# charivari.net
KiCad netlist of a schematic drawn in EAGLE
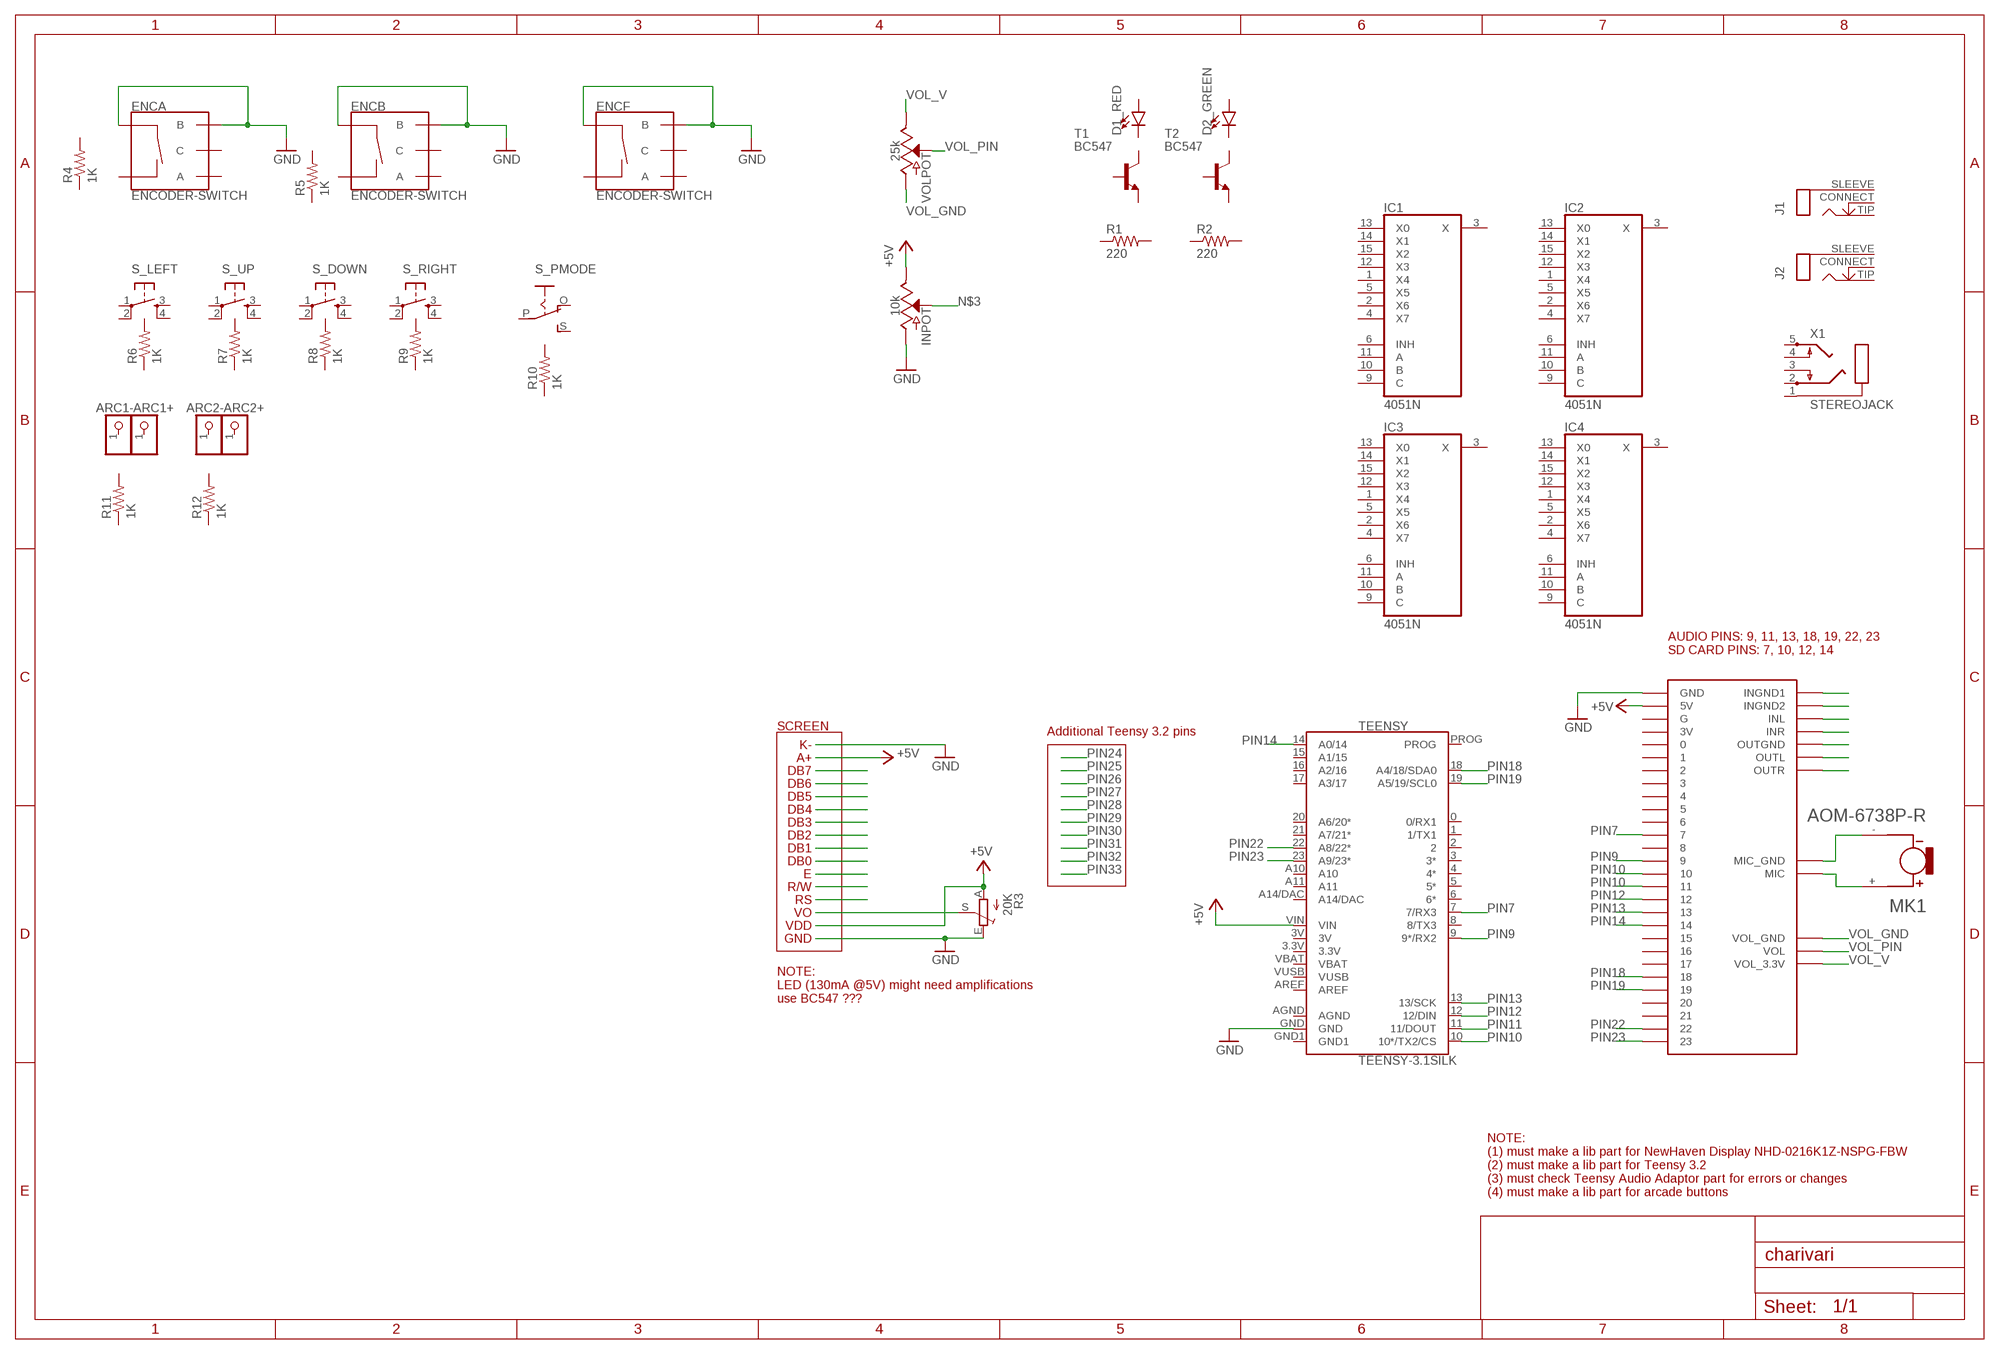
[diagram p0: schematic, sheet 1]

(export (version "E")
  (design (tool "Eeschema 10.0.6"))
  (components
    (comp (ref "ARC1+")
      (value "PINHD-1X1")
      (footprint "eagle-import:1X01")
      (libsource (lib "eagle-import") (part "PINHD-1X1"))
    )
    (comp (ref "ARC1-")
      (value "PINHD-1X1")
      (footprint "eagle-import:1X01")
      (libsource (lib "eagle-import") (part "PINHD-1X1"))
    )
    (comp (ref "ARC2+")
      (value "PINHD-1X1")
      (footprint "eagle-import:1X01")
      (libsource (lib "eagle-import") (part "PINHD-1X1"))
    )
    (comp (ref "ARC2-")
      (value "PINHD-1X1")
      (footprint "eagle-import:1X01")
      (libsource (lib "eagle-import") (part "PINHD-1X1"))
    )
    (comp (ref "AUDIO_ADAPTOR")
      (value "AUDIOSHIELD")
      (footprint "eagle-import:AUDIOSHIELD")
      (libsource (lib "eagle-import") (part "AUDIOSHIELD"))
    )
    (comp (ref "D1_RED")
      (value "LED5MM")
      (footprint "eagle-import:LED_5MM")
      (libsource (lib "eagle-import") (part "LED5MM"))
    )
    (comp (ref "D2_GREEN")
      (value "LED5MM")
      (footprint "eagle-import:LED_5MM")
      (libsource (lib "eagle-import") (part "LED5MM"))
    )
    (comp (ref "ENCA")
      (value "ENCODER-SWITCH")
      (footprint "eagle-import:ROTARY_ENC_PLAIN")
      (libsource (lib "eagle-import") (part "ENCODER-SWITCH"))
    )
    (comp (ref "ENCB")
      (value "ENCODER-SWITCH")
      (footprint "eagle-import:ROTARY_ENC_PLAIN")
      (libsource (lib "eagle-import") (part "ENCODER-SWITCH"))
    )
    (comp (ref "ENCF")
      (value "ENCODER-SWITCH")
      (footprint "eagle-import:ROTARY_ENC_PLAIN")
      (libsource (lib "eagle-import") (part "ENCODER-SWITCH"))
    )
    (comp (ref "IC1")
      (value "4051N")
      (footprint "eagle-import:DIL16")
      (libsource (lib "eagle-import") (part "4051N"))
    )
    (comp (ref "IC2")
      (value "4051N")
      (footprint "eagle-import:DIL16")
      (libsource (lib "eagle-import") (part "4051N"))
    )
    (comp (ref "IC3")
      (value "4051N")
      (footprint "eagle-import:DIL16")
      (libsource (lib "eagle-import") (part "4051N"))
    )
    (comp (ref "IC4")
      (value "4051N")
      (footprint "eagle-import:DIL16")
      (libsource (lib "eagle-import") (part "4051N"))
    )
    (comp (ref "INPOT")
      (value "10k")
      (footprint "eagle-import:POT-PTH-ALPS-KIT")
      (libsource (lib "eagle-import") (part "POTENTIOMETER-PTH-9MM-1/20W-20%-KIT"))
    )
    (comp (ref "J1")
      (value "CLOSEDMONO")
      (footprint "eagle-import:CLOSED_MONO_JACK")
      (libsource (lib "eagle-import") (part "CLOSEDMONO"))
    )
    (comp (ref "J2")
      (value "CLOSEDMONO")
      (footprint "eagle-import:CLOSED_MONO_JACK")
      (libsource (lib "eagle-import") (part "CLOSEDMONO"))
    )
    (comp (ref "MK1")
      (value "AOM-6738P-R")
      (footprint "eagle-import:MIC_AOM-6738P-R")
      (fields (field (name "MF") "PUI"))
      (libsource (lib "eagle-import") (part "AOM-6738P-R"))
    )
    (comp (ref "R1")
      (value "220")
      (footprint "eagle-import:0204_7")
      (libsource (lib "eagle-import") (part "R-US_0204/7"))
    )
    (comp (ref "R2")
      (value "220")
      (footprint "eagle-import:0204_7")
      (libsource (lib "eagle-import") (part "R-US_0204/7"))
    )
    (comp (ref "R3")
      (value "20K")
      (footprint "eagle-import:B25P")
      (libsource (lib "eagle-import") (part "TRIM_EU-B25P"))
    )
    (comp (ref "R4")
      (value "1K")
      (footprint "eagle-import:0204_7")
      (libsource (lib "eagle-import") (part "R-US_0204/7"))
    )
    (comp (ref "R5")
      (value "1K")
      (footprint "eagle-import:0204_7")
      (libsource (lib "eagle-import") (part "R-US_0204/7"))
    )
    (comp (ref "R6")
      (value "1K")
      (footprint "eagle-import:0204_7")
      (libsource (lib "eagle-import") (part "R-US_0204/7"))
    )
    (comp (ref "R7")
      (value "1K")
      (footprint "eagle-import:0204_7")
      (libsource (lib "eagle-import") (part "R-US_0204/7"))
    )
    (comp (ref "R8")
      (value "1K")
      (footprint "eagle-import:0204_7")
      (libsource (lib "eagle-import") (part "R-US_0204/7"))
    )
    (comp (ref "R9")
      (value "1K")
      (footprint "eagle-import:0204_7")
      (libsource (lib "eagle-import") (part "R-US_0204/7"))
    )
    (comp (ref "R10")
      (value "1K")
      (footprint "eagle-import:0204_7")
      (libsource (lib "eagle-import") (part "R-US_0204/7"))
    )
    (comp (ref "R11")
      (value "1K")
      (footprint "eagle-import:0204_7")
      (libsource (lib "eagle-import") (part "R-US_0204/7"))
    )
    (comp (ref "R12")
      (value "1K")
      (footprint "eagle-import:0204_7")
      (libsource (lib "eagle-import") (part "R-US_0204/7"))
    )
    (comp (ref "S_DOWN")
      (value "TAC_SWITCHPTH")
      (footprint "eagle-import:TACTILE-PTH")
      (libsource (lib "eagle-import") (part "TAC_SWITCHPTH"))
    )
    (comp (ref "S_LEFT")
      (value "TAC_SWITCHPTH")
      (footprint "eagle-import:TACTILE-PTH")
      (libsource (lib "eagle-import") (part "TAC_SWITCHPTH"))
    )
    (comp (ref "S_PMODE")
      (value "EG1218S")
      (footprint "eagle-import:EG1218")
      (libsource (lib "eagle-import") (part "EG1218S"))
    )
    (comp (ref "S_RIGHT")
      (value "TAC_SWITCHPTH")
      (footprint "eagle-import:TACTILE-PTH")
      (libsource (lib "eagle-import") (part "TAC_SWITCHPTH"))
    )
    (comp (ref "S_UP")
      (value "TAC_SWITCHPTH")
      (footprint "eagle-import:TACTILE-PTH")
      (libsource (lib "eagle-import") (part "TAC_SWITCHPTH"))
    )
    (comp (ref "T1")
      (value "BC547")
      (footprint "eagle-import:TO92")
      (libsource (lib "eagle-import") (part "BC547"))
    )
    (comp (ref "T2")
      (value "BC547")
      (footprint "eagle-import:TO92")
      (libsource (lib "eagle-import") (part "BC547"))
    )
    (comp (ref "TEENSY")
      (value "TEENSY-3.1SILK")
      (footprint "eagle-import:TEENSY-3.1")
      (libsource (lib "eagle-import") (part "TEENSY-3.1SILK"))
    )
    (comp (ref "VOLPOT")
      (value "25k")
      (footprint "eagle-import:POT-PTH-ALPS-KIT")
      (libsource (lib "eagle-import") (part "POTENTIOMETER-PTH-9MM-1/20W-20%-KIT"))
    )
    (comp (ref "X1")
      (value "STEREOJACK")
      (footprint "eagle-import:STX3100")
      (libsource (lib "eagle-import") (part "STEREOJACK"))
    )
  )
  (nets
    (net (code "1") (name "+5V") (class "Default")
      (node (ref "AUDIO_ADAPTOR") (pin "5V") (pinfunction "5V_5V") (pintype "bidirectional"))
      (node (ref "INPOT") (pin "P$1") (pinfunction "E_P$1") (pintype "passive"))
      (node (ref "R3") (pin "A") (pinfunction "A_A") (pintype "passive"))
      (node (ref "TEENSY") (pin "VIN") (pinfunction "VIN_VIN") (pintype "power_in"))
    )
    (net (code "2") (name "/3.3V") (class "Default")
      (node (ref "TEENSY") (pin "3.3V") (pinfunction "3.3V_3.3V") (pintype "power_in"))
    )
    (net (code "3") (name "/3V") (class "Default")
      (node (ref "TEENSY") (pin "3V") (pinfunction "3V_3V") (pintype "power_in"))
    )
    (net (code "4") (name "/AGND") (class "Default")
      (node (ref "TEENSY") (pin "AGND") (pinfunction "AGND_AGND") (pintype "power_in"))
    )
    (net (code "5") (name "/GND1") (class "Default")
      (node (ref "TEENSY") (pin "GND1") (pinfunction "GND1_GND1") (pintype "power_in"))
    )
    (net (code "6") (name "/N$3") (class "Default")
      (node (ref "INPOT") (pin "P$2") (pinfunction "S_P$2") (pintype "passive"))
    )
    (net (code "7") (name "/PIN7") (class "Default")
      (node (ref "AUDIO_ADAPTOR") (pin "7") (pinfunction "7_7") (pintype "bidirectional"))
      (node (ref "TEENSY") (pin "7") (pinfunction "7/RX3_7") (pintype "bidirectional"))
    )
    (net (code "8") (name "/PIN9") (class "Default")
      (node (ref "AUDIO_ADAPTOR") (pin "9") (pinfunction "9_9") (pintype "bidirectional"))
      (node (ref "TEENSY") (pin "9") (pinfunction "9*/RX2_9") (pintype "bidirectional"))
    )
    (net (code "9") (name "/PIN10") (class "Default")
      (node (ref "AUDIO_ADAPTOR") (pin "10") (pinfunction "10_10") (pintype "bidirectional"))
      (node (ref "AUDIO_ADAPTOR") (pin "11") (pinfunction "11_11") (pintype "bidirectional"))
      (node (ref "TEENSY") (pin "10") (pinfunction "10*/TX2/CS_10") (pintype "bidirectional"))
    )
    (net (code "10") (name "/PIN11") (class "Default")
      (node (ref "TEENSY") (pin "11") (pinfunction "11/DOUT_11") (pintype "bidirectional"))
    )
    (net (code "11") (name "/PIN12") (class "Default")
      (node (ref "AUDIO_ADAPTOR") (pin "12") (pinfunction "12_12") (pintype "bidirectional"))
      (node (ref "TEENSY") (pin "12") (pinfunction "12/DIN_12") (pintype "bidirectional"))
    )
    (net (code "12") (name "/PIN13") (class "Default")
      (node (ref "AUDIO_ADAPTOR") (pin "13") (pinfunction "13_13") (pintype "bidirectional"))
      (node (ref "TEENSY") (pin "13") (pinfunction "13/SCK_13") (pintype "bidirectional"))
    )
    (net (code "13") (name "/PIN14") (class "Default")
      (node (ref "AUDIO_ADAPTOR") (pin "14") (pinfunction "14_14") (pintype "bidirectional"))
      (node (ref "TEENSY") (pin "14") (pinfunction "A0/14_14") (pintype "bidirectional"))
    )
    (net (code "14") (name "/PIN18") (class "Default")
      (node (ref "AUDIO_ADAPTOR") (pin "18") (pinfunction "18_18") (pintype "bidirectional"))
      (node (ref "TEENSY") (pin "18") (pinfunction "A4/18/SDA0_18") (pintype "bidirectional"))
    )
    (net (code "15") (name "/PIN19") (class "Default")
      (node (ref "AUDIO_ADAPTOR") (pin "19") (pinfunction "19_19") (pintype "bidirectional"))
      (node (ref "TEENSY") (pin "19") (pinfunction "A5/19/SCL0_19") (pintype "bidirectional"))
    )
    (net (code "16") (name "/PIN22") (class "Default")
      (node (ref "AUDIO_ADAPTOR") (pin "22") (pinfunction "22_22") (pintype "bidirectional"))
      (node (ref "TEENSY") (pin "22") (pinfunction "A8/22*_22") (pintype "bidirectional"))
    )
    (net (code "17") (name "/PIN23") (class "Default")
      (node (ref "AUDIO_ADAPTOR") (pin "23") (pinfunction "23_23") (pintype "bidirectional"))
      (node (ref "TEENSY") (pin "23") (pinfunction "A9/23*_23") (pintype "bidirectional"))
    )
    (net (code "28") (name "/VBAT") (class "Default")
      (node (ref "TEENSY") (pin "VBAT") (pinfunction "VBAT_VBAT") (pintype "power_in"))
    )
    (net (code "29") (name "/VOL_GND") (class "Default")
      (node (ref "AUDIO_ADAPTOR") (pin "VOL_GND") (pinfunction "VOL_GND_VOL_GND") (pintype "bidirectional"))
      (node (ref "VOLPOT") (pin "P$3") (pinfunction "A_P$3") (pintype "passive"))
    )
    (net (code "30") (name "/VOL_PIN") (class "Default")
      (node (ref "AUDIO_ADAPTOR") (pin "VOL") (pinfunction "VOL_VOL") (pintype "input"))
      (node (ref "VOLPOT") (pin "P$2") (pinfunction "S_P$2") (pintype "passive"))
    )
    (net (code "31") (name "/VOL_V") (class "Default")
      (node (ref "AUDIO_ADAPTOR") (pin "VOL_3.3V") (pinfunction "VOL_3.3V_VOL_3.3V") (pintype "bidirectional"))
      (node (ref "VOLPOT") (pin "P$1") (pinfunction "E_P$1") (pintype "passive"))
    )
    (net (code "32") (name "/VUSB") (class "Default")
      (node (ref "TEENSY") (pin "VUSB") (pinfunction "VUSB_VUSB") (pintype "power_in"))
    )
    (net (code "33") (name "GND") (class "Default")
      (node (ref "AUDIO_ADAPTOR") (pin "GND") (pinfunction "GND_GND") (pintype "bidirectional"))
      (node (ref "ENCA") (pin "B") (pinfunction "B_B") (pintype "bidirectional"))
      (node (ref "ENCA") (pin "SW+") (pinfunction "SW+_SW+") (pintype "bidirectional"))
      (node (ref "ENCB") (pin "B") (pinfunction "B_B") (pintype "bidirectional"))
      (node (ref "ENCB") (pin "SW+") (pinfunction "SW+_SW+") (pintype "bidirectional"))
      (node (ref "ENCF") (pin "B") (pinfunction "B_B") (pintype "bidirectional"))
      (node (ref "ENCF") (pin "SW+") (pinfunction "SW+_SW+") (pintype "bidirectional"))
      (node (ref "INPOT") (pin "P$3") (pinfunction "A_P$3") (pintype "passive"))
      (node (ref "R3") (pin "E") (pinfunction "E_E") (pintype "passive"))
      (node (ref "TEENSY") (pin "GND") (pinfunction "GND_GND") (pintype "power_in"))
    )
    (net (code "34") (name "Net-(AUDIO_ADAPTOR-MIC_GND)") (class "Default")
      (node (ref "AUDIO_ADAPTOR") (pin "GND_MIC") (pinfunction "MIC_GND_GND_MIC") (pintype "bidirectional"))
      (node (ref "MK1") (pin "-") (pinfunction "-_-") (pintype "passive"))
    )
    (net (code "35") (name "Net-(AUDIO_ADAPTOR-PadMIC)") (class "Default")
      (node (ref "AUDIO_ADAPTOR") (pin "MIC") (pinfunction "MIC_MIC") (pintype "input"))
      (node (ref "MK1") (pin "+") (pinfunction "+_+") (pintype "passive"))
    )
    (net (code "36") (name "unconnected-(ARC1+-Pad1)") (class "Default")
      (node (ref "ARC1+") (pin "1") (pinfunction "1_1") (pintype "passive"))
    )
    (net (code "37") (name "unconnected-(ARC1--Pad1)") (class "Default")
      (node (ref "ARC1-") (pin "1") (pinfunction "1_1") (pintype "passive"))
    )
    (net (code "38") (name "unconnected-(ARC2+-Pad1)") (class "Default")
      (node (ref "ARC2+") (pin "1") (pinfunction "1_1") (pintype "passive"))
    )
    (net (code "39") (name "unconnected-(ARC2--Pad1)") (class "Default")
      (node (ref "ARC2-") (pin "1") (pinfunction "1_1") (pintype "passive"))
    )
    (net (code "40") (name "unconnected-(AUDIO_ADAPTOR-Pad0)") (class "Default")
      (node (ref "AUDIO_ADAPTOR") (pin "0") (pinfunction "0_0") (pintype "bidirectional"))
    )
    (net (code "41") (name "unconnected-(AUDIO_ADAPTOR-Pad1)") (class "Default")
      (node (ref "AUDIO_ADAPTOR") (pin "1") (pinfunction "1_1") (pintype "bidirectional"))
    )
    (net (code "42") (name "unconnected-(AUDIO_ADAPTOR-Pad2)") (class "Default")
      (node (ref "AUDIO_ADAPTOR") (pin "2") (pinfunction "2_2") (pintype "bidirectional"))
    )
    (net (code "43") (name "unconnected-(AUDIO_ADAPTOR-Pad3)") (class "Default")
      (node (ref "AUDIO_ADAPTOR") (pin "3") (pinfunction "3_3") (pintype "bidirectional"))
    )
    (net (code "44") (name "unconnected-(AUDIO_ADAPTOR-Pad3V)") (class "Default")
      (node (ref "AUDIO_ADAPTOR") (pin "3V") (pinfunction "3V_3V") (pintype "bidirectional"))
    )
    (net (code "45") (name "unconnected-(AUDIO_ADAPTOR-Pad4)") (class "Default")
      (node (ref "AUDIO_ADAPTOR") (pin "4") (pinfunction "4_4") (pintype "bidirectional"))
    )
    (net (code "46") (name "unconnected-(AUDIO_ADAPTOR-Pad5)") (class "Default")
      (node (ref "AUDIO_ADAPTOR") (pin "5") (pinfunction "5_5") (pintype "bidirectional"))
    )
    (net (code "47") (name "unconnected-(AUDIO_ADAPTOR-Pad6)") (class "Default")
      (node (ref "AUDIO_ADAPTOR") (pin "6") (pinfunction "6_6") (pintype "bidirectional"))
    )
    (net (code "48") (name "unconnected-(AUDIO_ADAPTOR-Pad8)") (class "Default")
      (node (ref "AUDIO_ADAPTOR") (pin "8") (pinfunction "8_8") (pintype "bidirectional"))
    )
    (net (code "49") (name "unconnected-(AUDIO_ADAPTOR-Pad15)") (class "Default")
      (node (ref "AUDIO_ADAPTOR") (pin "15") (pinfunction "15_15") (pintype "bidirectional"))
    )
    (net (code "50") (name "unconnected-(AUDIO_ADAPTOR-Pad16)") (class "Default")
      (node (ref "AUDIO_ADAPTOR") (pin "16") (pinfunction "16_16") (pintype "bidirectional"))
    )
    (net (code "51") (name "unconnected-(AUDIO_ADAPTOR-Pad17)") (class "Default")
      (node (ref "AUDIO_ADAPTOR") (pin "17") (pinfunction "17_17") (pintype "bidirectional"))
    )
    (net (code "52") (name "unconnected-(AUDIO_ADAPTOR-Pad20)") (class "Default")
      (node (ref "AUDIO_ADAPTOR") (pin "20") (pinfunction "20_20") (pintype "bidirectional"))
    )
    (net (code "53") (name "unconnected-(AUDIO_ADAPTOR-Pad21)") (class "Default")
      (node (ref "AUDIO_ADAPTOR") (pin "21") (pinfunction "21_21") (pintype "bidirectional"))
    )
    (net (code "54") (name "unconnected-(AUDIO_ADAPTOR-PadG)") (class "Default")
      (node (ref "AUDIO_ADAPTOR") (pin "G") (pinfunction "G_G") (pintype "bidirectional"))
    )
    (net (code "55") (name "unconnected-(AUDIO_ADAPTOR-PadINGND1)") (class "Default")
      (node (ref "AUDIO_ADAPTOR") (pin "INGND1") (pinfunction "INGND1_INGND1") (pintype "bidirectional"))
    )
    (net (code "56") (name "unconnected-(AUDIO_ADAPTOR-PadINGND2)") (class "Default")
      (node (ref "AUDIO_ADAPTOR") (pin "INGND2") (pinfunction "INGND2_INGND2") (pintype "bidirectional"))
    )
    (net (code "57") (name "unconnected-(AUDIO_ADAPTOR-PadINL)") (class "Default")
      (node (ref "AUDIO_ADAPTOR") (pin "INL") (pinfunction "INL_INL") (pintype "input"))
    )
    (net (code "58") (name "unconnected-(AUDIO_ADAPTOR-PadINR)") (class "Default")
      (node (ref "AUDIO_ADAPTOR") (pin "INR") (pinfunction "INR_INR") (pintype "input"))
    )
    (net (code "59") (name "unconnected-(AUDIO_ADAPTOR-PadOUTGND)") (class "Default")
      (node (ref "AUDIO_ADAPTOR") (pin "OUTGND") (pinfunction "OUTGND_OUTGND") (pintype "bidirectional"))
    )
    (net (code "60") (name "unconnected-(AUDIO_ADAPTOR-PadOUTL)") (class "Default")
      (node (ref "AUDIO_ADAPTOR") (pin "OUTL") (pinfunction "OUTL_OUTL") (pintype "output"))
    )
    (net (code "61") (name "unconnected-(AUDIO_ADAPTOR-PadOUTR)") (class "Default")
      (node (ref "AUDIO_ADAPTOR") (pin "OUTR") (pinfunction "OUTR_OUTR") (pintype "output"))
    )
    (net (code "62") (name "unconnected-(D1_RED-C-PadK)") (class "Default")
      (node (ref "D1_RED") (pin "K") (pinfunction "C_K") (pintype "passive"))
    )
    (net (code "63") (name "unconnected-(D1_RED-PadA)") (class "Default")
      (node (ref "D1_RED") (pin "A") (pinfunction "A_A") (pintype "passive"))
    )
    (net (code "64") (name "unconnected-(D2_GREEN-C-PadK)") (class "Default")
      (node (ref "D2_GREEN") (pin "K") (pinfunction "C_K") (pintype "passive"))
    )
    (net (code "65") (name "unconnected-(D2_GREEN-PadA)") (class "Default")
      (node (ref "D2_GREEN") (pin "A") (pinfunction "A_A") (pintype "passive"))
    )
    (net (code "66") (name "unconnected-(ENCA-PadA)") (class "Default")
      (node (ref "ENCA") (pin "A") (pinfunction "A_A") (pintype "bidirectional"))
    )
    (net (code "67") (name "unconnected-(ENCA-PadC)") (class "Default")
      (node (ref "ENCA") (pin "C") (pinfunction "C_C") (pintype "bidirectional"))
    )
    (net (code "68") (name "unconnected-(ENCA-PadSW-)") (class "Default")
      (node (ref "ENCA") (pin "SW-") (pinfunction "SW-_SW-") (pintype "bidirectional"))
    )
    (net (code "69") (name "unconnected-(ENCB-PadA)") (class "Default")
      (node (ref "ENCB") (pin "A") (pinfunction "A_A") (pintype "bidirectional"))
    )
    (net (code "70") (name "unconnected-(ENCB-PadC)") (class "Default")
      (node (ref "ENCB") (pin "C") (pinfunction "C_C") (pintype "bidirectional"))
    )
    (net (code "71") (name "unconnected-(ENCB-PadSW-)") (class "Default")
      (node (ref "ENCB") (pin "SW-") (pinfunction "SW-_SW-") (pintype "bidirectional"))
    )
    (net (code "72") (name "unconnected-(ENCF-PadA)") (class "Default")
      (node (ref "ENCF") (pin "A") (pinfunction "A_A") (pintype "bidirectional"))
    )
    (net (code "73") (name "unconnected-(ENCF-PadC)") (class "Default")
      (node (ref "ENCF") (pin "C") (pinfunction "C_C") (pintype "bidirectional"))
    )
    (net (code "74") (name "unconnected-(ENCF-PadSW-)") (class "Default")
      (node (ref "ENCF") (pin "SW-") (pinfunction "SW-_SW-") (pintype "bidirectional"))
    )
    (net (code "75") (name "unconnected-(IC1A-A-Pad11)") (class "Default")
      (node (ref "IC1") (pin "11") (pinfunction "A_11") (pintype "input"))
    )
    (net (code "76") (name "unconnected-(IC1A-B-Pad10)") (class "Default")
      (node (ref "IC1") (pin "10") (pinfunction "B_10") (pintype "input"))
    )
    (net (code "77") (name "unconnected-(IC1A-C-Pad9)") (class "Default")
      (node (ref "IC1") (pin "9") (pinfunction "C_9") (pintype "input"))
    )
    (net (code "78") (name "unconnected-(IC1A-INH-Pad6)") (class "Default")
      (node (ref "IC1") (pin "6") (pinfunction "INH_6") (pintype "input"))
    )
    (net (code "79") (name "unconnected-(IC1A-X-Pad3)") (class "Default")
      (node (ref "IC1") (pin "3") (pinfunction "X_3") (pintype "bidirectional"))
    )
    (net (code "80") (name "unconnected-(IC1A-X0-Pad13)") (class "Default")
      (node (ref "IC1") (pin "13") (pinfunction "X0_13") (pintype "bidirectional"))
    )
    (net (code "81") (name "unconnected-(IC1A-X1-Pad14)") (class "Default")
      (node (ref "IC1") (pin "14") (pinfunction "X1_14") (pintype "bidirectional"))
    )
    (net (code "82") (name "unconnected-(IC1A-X2-Pad15)") (class "Default")
      (node (ref "IC1") (pin "15") (pinfunction "X2_15") (pintype "bidirectional"))
    )
    (net (code "83") (name "unconnected-(IC1A-X3-Pad12)") (class "Default")
      (node (ref "IC1") (pin "12") (pinfunction "X3_12") (pintype "bidirectional"))
    )
    (net (code "84") (name "unconnected-(IC1A-X4-Pad1)") (class "Default")
      (node (ref "IC1") (pin "1") (pinfunction "X4_1") (pintype "bidirectional"))
    )
    (net (code "85") (name "unconnected-(IC1A-X5-Pad5)") (class "Default")
      (node (ref "IC1") (pin "5") (pinfunction "X5_5") (pintype "bidirectional"))
    )
    (net (code "86") (name "unconnected-(IC1A-X6-Pad2)") (class "Default")
      (node (ref "IC1") (pin "2") (pinfunction "X6_2") (pintype "bidirectional"))
    )
    (net (code "87") (name "unconnected-(IC1A-X7-Pad4)") (class "Default")
      (node (ref "IC1") (pin "4") (pinfunction "X7_4") (pintype "bidirectional"))
    )
    (net (code "88") (name "unconnected-(IC2A-A-Pad11)") (class "Default")
      (node (ref "IC2") (pin "11") (pinfunction "A_11") (pintype "input"))
    )
    (net (code "89") (name "unconnected-(IC2A-B-Pad10)") (class "Default")
      (node (ref "IC2") (pin "10") (pinfunction "B_10") (pintype "input"))
    )
    (net (code "90") (name "unconnected-(IC2A-C-Pad9)") (class "Default")
      (node (ref "IC2") (pin "9") (pinfunction "C_9") (pintype "input"))
    )
    (net (code "91") (name "unconnected-(IC2A-INH-Pad6)") (class "Default")
      (node (ref "IC2") (pin "6") (pinfunction "INH_6") (pintype "input"))
    )
    (net (code "92") (name "unconnected-(IC2A-X-Pad3)") (class "Default")
      (node (ref "IC2") (pin "3") (pinfunction "X_3") (pintype "bidirectional"))
    )
    (net (code "93") (name "unconnected-(IC2A-X0-Pad13)") (class "Default")
      (node (ref "IC2") (pin "13") (pinfunction "X0_13") (pintype "bidirectional"))
    )
    (net (code "94") (name "unconnected-(IC2A-X1-Pad14)") (class "Default")
      (node (ref "IC2") (pin "14") (pinfunction "X1_14") (pintype "bidirectional"))
    )
    (net (code "95") (name "unconnected-(IC2A-X2-Pad15)") (class "Default")
      (node (ref "IC2") (pin "15") (pinfunction "X2_15") (pintype "bidirectional"))
    )
    (net (code "96") (name "unconnected-(IC2A-X3-Pad12)") (class "Default")
      (node (ref "IC2") (pin "12") (pinfunction "X3_12") (pintype "bidirectional"))
    )
    (net (code "97") (name "unconnected-(IC2A-X4-Pad1)") (class "Default")
      (node (ref "IC2") (pin "1") (pinfunction "X4_1") (pintype "bidirectional"))
    )
    (net (code "98") (name "unconnected-(IC2A-X5-Pad5)") (class "Default")
      (node (ref "IC2") (pin "5") (pinfunction "X5_5") (pintype "bidirectional"))
    )
    (net (code "99") (name "unconnected-(IC2A-X6-Pad2)") (class "Default")
      (node (ref "IC2") (pin "2") (pinfunction "X6_2") (pintype "bidirectional"))
    )
    (net (code "100") (name "unconnected-(IC2A-X7-Pad4)") (class "Default")
      (node (ref "IC2") (pin "4") (pinfunction "X7_4") (pintype "bidirectional"))
    )
    (net (code "101") (name "unconnected-(IC3A-A-Pad11)") (class "Default")
      (node (ref "IC3") (pin "11") (pinfunction "A_11") (pintype "input"))
    )
    (net (code "102") (name "unconnected-(IC3A-B-Pad10)") (class "Default")
      (node (ref "IC3") (pin "10") (pinfunction "B_10") (pintype "input"))
    )
    (net (code "103") (name "unconnected-(IC3A-C-Pad9)") (class "Default")
      (node (ref "IC3") (pin "9") (pinfunction "C_9") (pintype "input"))
    )
    (net (code "104") (name "unconnected-(IC3A-INH-Pad6)") (class "Default")
      (node (ref "IC3") (pin "6") (pinfunction "INH_6") (pintype "input"))
    )
    (net (code "105") (name "unconnected-(IC3A-X-Pad3)") (class "Default")
      (node (ref "IC3") (pin "3") (pinfunction "X_3") (pintype "bidirectional"))
    )
    (net (code "106") (name "unconnected-(IC3A-X0-Pad13)") (class "Default")
      (node (ref "IC3") (pin "13") (pinfunction "X0_13") (pintype "bidirectional"))
    )
    (net (code "107") (name "unconnected-(IC3A-X1-Pad14)") (class "Default")
      (node (ref "IC3") (pin "14") (pinfunction "X1_14") (pintype "bidirectional"))
    )
    (net (code "108") (name "unconnected-(IC3A-X2-Pad15)") (class "Default")
      (node (ref "IC3") (pin "15") (pinfunction "X2_15") (pintype "bidirectional"))
    )
    (net (code "109") (name "unconnected-(IC3A-X3-Pad12)") (class "Default")
      (node (ref "IC3") (pin "12") (pinfunction "X3_12") (pintype "bidirectional"))
    )
    (net (code "110") (name "unconnected-(IC3A-X4-Pad1)") (class "Default")
      (node (ref "IC3") (pin "1") (pinfunction "X4_1") (pintype "bidirectional"))
    )
    (net (code "111") (name "unconnected-(IC3A-X5-Pad5)") (class "Default")
      (node (ref "IC3") (pin "5") (pinfunction "X5_5") (pintype "bidirectional"))
    )
    (net (code "112") (name "unconnected-(IC3A-X6-Pad2)") (class "Default")
      (node (ref "IC3") (pin "2") (pinfunction "X6_2") (pintype "bidirectional"))
    )
    (net (code "113") (name "unconnected-(IC3A-X7-Pad4)") (class "Default")
      (node (ref "IC3") (pin "4") (pinfunction "X7_4") (pintype "bidirectional"))
    )
    (net (code "114") (name "unconnected-(IC4A-A-Pad11)") (class "Default")
      (node (ref "IC4") (pin "11") (pinfunction "A_11") (pintype "input"))
    )
    (net (code "115") (name "unconnected-(IC4A-B-Pad10)") (class "Default")
      (node (ref "IC4") (pin "10") (pinfunction "B_10") (pintype "input"))
    )
    (net (code "116") (name "unconnected-(IC4A-C-Pad9)") (class "Default")
      (node (ref "IC4") (pin "9") (pinfunction "C_9") (pintype "input"))
    )
    (net (code "117") (name "unconnected-(IC4A-INH-Pad6)") (class "Default")
      (node (ref "IC4") (pin "6") (pinfunction "INH_6") (pintype "input"))
    )
    (net (code "118") (name "unconnected-(IC4A-X-Pad3)") (class "Default")
      (node (ref "IC4") (pin "3") (pinfunction "X_3") (pintype "bidirectional"))
    )
    (net (code "119") (name "unconnected-(IC4A-X0-Pad13)") (class "Default")
      (node (ref "IC4") (pin "13") (pinfunction "X0_13") (pintype "bidirectional"))
    )
    (net (code "120") (name "unconnected-(IC4A-X1-Pad14)") (class "Default")
      (node (ref "IC4") (pin "14") (pinfunction "X1_14") (pintype "bidirectional"))
    )
    (net (code "121") (name "unconnected-(IC4A-X2-Pad15)") (class "Default")
      (node (ref "IC4") (pin "15") (pinfunction "X2_15") (pintype "bidirectional"))
    )
    (net (code "122") (name "unconnected-(IC4A-X3-Pad12)") (class "Default")
      (node (ref "IC4") (pin "12") (pinfunction "X3_12") (pintype "bidirectional"))
    )
    (net (code "123") (name "unconnected-(IC4A-X4-Pad1)") (class "Default")
      (node (ref "IC4") (pin "1") (pinfunction "X4_1") (pintype "bidirectional"))
    )
    (net (code "124") (name "unconnected-(IC4A-X5-Pad5)") (class "Default")
      (node (ref "IC4") (pin "5") (pinfunction "X5_5") (pintype "bidirectional"))
    )
    (net (code "125") (name "unconnected-(IC4A-X6-Pad2)") (class "Default")
      (node (ref "IC4") (pin "2") (pinfunction "X6_2") (pintype "bidirectional"))
    )
    (net (code "126") (name "unconnected-(IC4A-X7-Pad4)") (class "Default")
      (node (ref "IC4") (pin "4") (pinfunction "X7_4") (pintype "bidirectional"))
    )
    (net (code "127") (name "unconnected-(J1-PadCONNECT)") (class "Default")
      (node (ref "J1") (pin "CONNECT") (pinfunction "CONNECT_CONNECT") (pintype "passive"))
    )
    (net (code "128") (name "unconnected-(J1-PadTIP)") (class "Default")
      (node (ref "J1") (pin "TIP") (pinfunction "TIP_TIP") (pintype "passive"))
    )
    (net (code "129") (name "unconnected-(J1-RING-PadSLEEVE)") (class "Default")
      (node (ref "J1") (pin "SLEEVE") (pinfunction "RING_SLEEVE") (pintype "passive"))
    )
    (net (code "130") (name "unconnected-(J2-PadCONNECT)") (class "Default")
      (node (ref "J2") (pin "CONNECT") (pinfunction "CONNECT_CONNECT") (pintype "passive"))
    )
    (net (code "131") (name "unconnected-(J2-PadTIP)") (class "Default")
      (node (ref "J2") (pin "TIP") (pinfunction "TIP_TIP") (pintype "passive"))
    )
    (net (code "132") (name "unconnected-(J2-RING-PadSLEEVE)") (class "Default")
      (node (ref "J2") (pin "SLEEVE") (pinfunction "RING_SLEEVE") (pintype "passive"))
    )
    (net (code "133") (name "unconnected-(R1-Pad1)") (class "Default")
      (node (ref "R1") (pin "1") (pinfunction "1_1") (pintype "passive"))
    )
    (net (code "134") (name "unconnected-(R1-Pad2)") (class "Default")
      (node (ref "R1") (pin "2") (pinfunction "2_2") (pintype "passive"))
    )
    (net (code "135") (name "unconnected-(R2-Pad1)") (class "Default")
      (node (ref "R2") (pin "1") (pinfunction "1_1") (pintype "passive"))
    )
    (net (code "136") (name "unconnected-(R2-Pad2)") (class "Default")
      (node (ref "R2") (pin "2") (pinfunction "2_2") (pintype "passive"))
    )
    (net (code "137") (name "unconnected-(R3-PadS)") (class "Default")
      (node (ref "R3") (pin "S") (pinfunction "S_S") (pintype "passive"))
    )
    (net (code "138") (name "unconnected-(R4-Pad1)") (class "Default")
      (node (ref "R4") (pin "1") (pinfunction "1_1") (pintype "passive"))
    )
    (net (code "139") (name "unconnected-(R4-Pad2)") (class "Default")
      (node (ref "R4") (pin "2") (pinfunction "2_2") (pintype "passive"))
    )
    (net (code "140") (name "unconnected-(R5-Pad1)") (class "Default")
      (node (ref "R5") (pin "1") (pinfunction "1_1") (pintype "passive"))
    )
    (net (code "141") (name "unconnected-(R5-Pad2)") (class "Default")
      (node (ref "R5") (pin "2") (pinfunction "2_2") (pintype "passive"))
    )
    (net (code "142") (name "unconnected-(R6-Pad1)") (class "Default")
      (node (ref "R6") (pin "1") (pinfunction "1_1") (pintype "passive"))
    )
    (net (code "143") (name "unconnected-(R6-Pad2)") (class "Default")
      (node (ref "R6") (pin "2") (pinfunction "2_2") (pintype "passive"))
    )
    (net (code "144") (name "unconnected-(R7-Pad1)") (class "Default")
      (node (ref "R7") (pin "1") (pinfunction "1_1") (pintype "passive"))
    )
    (net (code "145") (name "unconnected-(R7-Pad2)") (class "Default")
      (node (ref "R7") (pin "2") (pinfunction "2_2") (pintype "passive"))
    )
    (net (code "146") (name "unconnected-(R8-Pad1)") (class "Default")
      (node (ref "R8") (pin "1") (pinfunction "1_1") (pintype "passive"))
    )
    (net (code "147") (name "unconnected-(R8-Pad2)") (class "Default")
      (node (ref "R8") (pin "2") (pinfunction "2_2") (pintype "passive"))
    )
    (net (code "148") (name "unconnected-(R9-Pad1)") (class "Default")
      (node (ref "R9") (pin "1") (pinfunction "1_1") (pintype "passive"))
    )
    (net (code "149") (name "unconnected-(R9-Pad2)") (class "Default")
      (node (ref "R9") (pin "2") (pinfunction "2_2") (pintype "passive"))
    )
    (net (code "150") (name "unconnected-(R10-Pad1)") (class "Default")
      (node (ref "R10") (pin "1") (pinfunction "1_1") (pintype "passive"))
    )
    (net (code "151") (name "unconnected-(R10-Pad2)") (class "Default")
      (node (ref "R10") (pin "2") (pinfunction "2_2") (pintype "passive"))
    )
    (net (code "152") (name "unconnected-(R11-Pad1)") (class "Default")
      (node (ref "R11") (pin "1") (pinfunction "1_1") (pintype "passive"))
    )
    (net (code "153") (name "unconnected-(R11-Pad2)") (class "Default")
      (node (ref "R11") (pin "2") (pinfunction "2_2") (pintype "passive"))
    )
    (net (code "154") (name "unconnected-(R12-Pad1)") (class "Default")
      (node (ref "R12") (pin "1") (pinfunction "1_1") (pintype "passive"))
    )
    (net (code "155") (name "unconnected-(R12-Pad2)") (class "Default")
      (node (ref "R12") (pin "2") (pinfunction "2_2") (pintype "passive"))
    )
    (net (code "156") (name "unconnected-(S_DOWN-Pad1)") (class "Default")
      (node (ref "S_DOWN") (pin "1") (pinfunction "1_1") (pintype "passive"))
    )
    (net (code "157") (name "unconnected-(S_DOWN-Pad2)") (class "Default")
      (node (ref "S_DOWN") (pin "2") (pinfunction "2_2") (pintype "passive"))
    )
    (net (code "158") (name "unconnected-(S_DOWN-Pad3)") (class "Default")
      (node (ref "S_DOWN") (pin "3") (pinfunction "3_3") (pintype "passive"))
    )
    (net (code "159") (name "unconnected-(S_DOWN-Pad4)") (class "Default")
      (node (ref "S_DOWN") (pin "4") (pinfunction "4_4") (pintype "passive"))
    )
    (net (code "160") (name "unconnected-(S_LEFT-Pad1)") (class "Default")
      (node (ref "S_LEFT") (pin "1") (pinfunction "1_1") (pintype "passive"))
    )
    (net (code "161") (name "unconnected-(S_LEFT-Pad2)") (class "Default")
      (node (ref "S_LEFT") (pin "2") (pinfunction "2_2") (pintype "passive"))
    )
    (net (code "162") (name "unconnected-(S_LEFT-Pad3)") (class "Default")
      (node (ref "S_LEFT") (pin "3") (pinfunction "3_3") (pintype "passive"))
    )
    (net (code "163") (name "unconnected-(S_LEFT-Pad4)") (class "Default")
      (node (ref "S_LEFT") (pin "4") (pinfunction "4_4") (pintype "passive"))
    )
    (net (code "164") (name "unconnected-(S_PMODE-PadO)") (class "Default")
      (node (ref "S_PMODE") (pin "O") (pinfunction "O_O") (pintype "passive"))
    )
    (net (code "165") (name "unconnected-(S_PMODE-PadP)") (class "Default")
      (node (ref "S_PMODE") (pin "P") (pinfunction "P_P") (pintype "passive"))
    )
    (net (code "166") (name "unconnected-(S_PMODE-PadS)") (class "Default")
      (node (ref "S_PMODE") (pin "S") (pinfunction "S_S") (pintype "passive"))
    )
    (net (code "167") (name "unconnected-(S_RIGHT-Pad1)") (class "Default")
      (node (ref "S_RIGHT") (pin "1") (pinfunction "1_1") (pintype "passive"))
    )
    (net (code "168") (name "unconnected-(S_RIGHT-Pad2)") (class "Default")
      (node (ref "S_RIGHT") (pin "2") (pinfunction "2_2") (pintype "passive"))
    )
    (net (code "169") (name "unconnected-(S_RIGHT-Pad3)") (class "Default")
      (node (ref "S_RIGHT") (pin "3") (pinfunction "3_3") (pintype "passive"))
    )
    (net (code "170") (name "unconnected-(S_RIGHT-Pad4)") (class "Default")
      (node (ref "S_RIGHT") (pin "4") (pinfunction "4_4") (pintype "passive"))
    )
    (net (code "171") (name "unconnected-(S_UP-Pad1)") (class "Default")
      (node (ref "S_UP") (pin "1") (pinfunction "1_1") (pintype "passive"))
    )
    (net (code "172") (name "unconnected-(S_UP-Pad2)") (class "Default")
      (node (ref "S_UP") (pin "2") (pinfunction "2_2") (pintype "passive"))
    )
    (net (code "173") (name "unconnected-(S_UP-Pad3)") (class "Default")
      (node (ref "S_UP") (pin "3") (pinfunction "3_3") (pintype "passive"))
    )
    (net (code "174") (name "unconnected-(S_UP-Pad4)") (class "Default")
      (node (ref "S_UP") (pin "4") (pinfunction "4_4") (pintype "passive"))
    )
    (net (code "175") (name "unconnected-(T1-B-Pad2)") (class "Default")
      (node (ref "T1") (pin "2") (pinfunction "B_2") (pintype "passive"))
    )
    (net (code "176") (name "unconnected-(T1-C-Pad3)") (class "Default")
      (node (ref "T1") (pin "3") (pinfunction "C_3") (pintype "passive"))
    )
    (net (code "177") (name "unconnected-(T1-E-Pad1)") (class "Default")
      (node (ref "T1") (pin "1") (pinfunction "E_1") (pintype "passive"))
    )
    (net (code "178") (name "unconnected-(T2-B-Pad2)") (class "Default")
      (node (ref "T2") (pin "2") (pinfunction "B_2") (pintype "passive"))
    )
    (net (code "179") (name "unconnected-(T2-C-Pad3)") (class "Default")
      (node (ref "T2") (pin "3") (pinfunction "C_3") (pintype "passive"))
    )
    (net (code "180") (name "unconnected-(T2-E-Pad1)") (class "Default")
      (node (ref "T2") (pin "1") (pinfunction "E_1") (pintype "passive"))
    )
    (net (code "181") (name "unconnected-(TEENSY-0{slash}RX1-Pad0)") (class "Default")
      (node (ref "TEENSY") (pin "0") (pinfunction "0/RX1_0") (pintype "bidirectional"))
    )
    (net (code "182") (name "unconnected-(TEENSY-1{slash}TX1-Pad1)") (class "Default")
      (node (ref "TEENSY") (pin "1") (pinfunction "1/TX1_1") (pintype "bidirectional"))
    )
    (net (code "183") (name "unconnected-(TEENSY-3*-Pad3)") (class "Default")
      (node (ref "TEENSY") (pin "3") (pinfunction "3*_3") (pintype "bidirectional"))
    )
    (net (code "184") (name "unconnected-(TEENSY-4*-Pad4)") (class "Default")
      (node (ref "TEENSY") (pin "4") (pinfunction "4*_4") (pintype "bidirectional"))
    )
    (net (code "185") (name "unconnected-(TEENSY-5*-Pad5)") (class "Default")
      (node (ref "TEENSY") (pin "5") (pinfunction "5*_5") (pintype "bidirectional"))
    )
    (net (code "186") (name "unconnected-(TEENSY-6*-Pad6)") (class "Default")
      (node (ref "TEENSY") (pin "6") (pinfunction "6*_6") (pintype "bidirectional"))
    )
    (net (code "187") (name "unconnected-(TEENSY-8{slash}TX3-Pad8)") (class "Default")
      (node (ref "TEENSY") (pin "8") (pinfunction "8/TX3_8") (pintype "bidirectional"))
    )
    (net (code "188") (name "unconnected-(TEENSY-A1{slash}15-Pad15)") (class "Default")
      (node (ref "TEENSY") (pin "15") (pinfunction "A1/15_15") (pintype "bidirectional"))
    )
    (net (code "189") (name "unconnected-(TEENSY-A2{slash}16-Pad16)") (class "Default")
      (node (ref "TEENSY") (pin "16") (pinfunction "A2/16_16") (pintype "bidirectional"))
    )
    (net (code "190") (name "unconnected-(TEENSY-A3{slash}17-Pad17)") (class "Default")
      (node (ref "TEENSY") (pin "17") (pinfunction "A3/17_17") (pintype "bidirectional"))
    )
    (net (code "191") (name "unconnected-(TEENSY-A6{slash}20*-Pad20)") (class "Default")
      (node (ref "TEENSY") (pin "20") (pinfunction "A6/20*_20") (pintype "bidirectional"))
    )
    (net (code "192") (name "unconnected-(TEENSY-A7{slash}21*-Pad21)") (class "Default")
      (node (ref "TEENSY") (pin "21") (pinfunction "A7/21*_21") (pintype "bidirectional"))
    )
    (net (code "193") (name "unconnected-(TEENSY-Pad2)") (class "Default")
      (node (ref "TEENSY") (pin "2") (pinfunction "2_2") (pintype "bidirectional"))
    )
    (net (code "194") (name "unconnected-(TEENSY-PadA10)") (class "Default")
      (node (ref "TEENSY") (pin "A10") (pinfunction "A10_A10") (pintype "bidirectional"))
    )
    (net (code "195") (name "unconnected-(TEENSY-PadA11)") (class "Default")
      (node (ref "TEENSY") (pin "A11") (pinfunction "A11_A11") (pintype "bidirectional"))
    )
    (net (code "196") (name "unconnected-(TEENSY-PadA14{slash}DAC)") (class "Default")
      (node (ref "TEENSY") (pin "A14/DAC") (pinfunction "A14/DAC_A14/DAC") (pintype "bidirectional"))
    )
    (net (code "197") (name "unconnected-(TEENSY-PadAREF)") (class "Default")
      (node (ref "TEENSY") (pin "AREF") (pinfunction "AREF_AREF") (pintype "bidirectional"))
    )
    (net (code "198") (name "unconnected-(TEENSY-PadPROG)") (class "Default")
      (node (ref "TEENSY") (pin "PROG") (pinfunction "PROG_PROG") (pintype "bidirectional"))
    )
    (net (code "199") (name "unconnected-(X1-Pad1)") (class "Default")
      (node (ref "X1") (pin "1") (pinfunction "1_1") (pintype "passive"))
    )
    (net (code "200") (name "unconnected-(X1-Pad2)") (class "Default")
      (node (ref "X1") (pin "2") (pinfunction "2_2") (pintype "passive"))
    )
    (net (code "201") (name "unconnected-(X1-Pad3)") (class "Default")
      (node (ref "X1") (pin "3") (pinfunction "3_3") (pintype "passive"))
    )
    (net (code "202") (name "unconnected-(X1-Pad4)") (class "Default")
      (node (ref "X1") (pin "4") (pinfunction "4_4") (pintype "passive"))
    )
    (net (code "203") (name "unconnected-(X1-Pad5)") (class "Default")
      (node (ref "X1") (pin "5") (pinfunction "5_5") (pintype "passive"))
    )
  )
)
